# RBB_MCU7_V2_2_MCU.net
KiCad netlist of a schematic drawn in Altium Designer
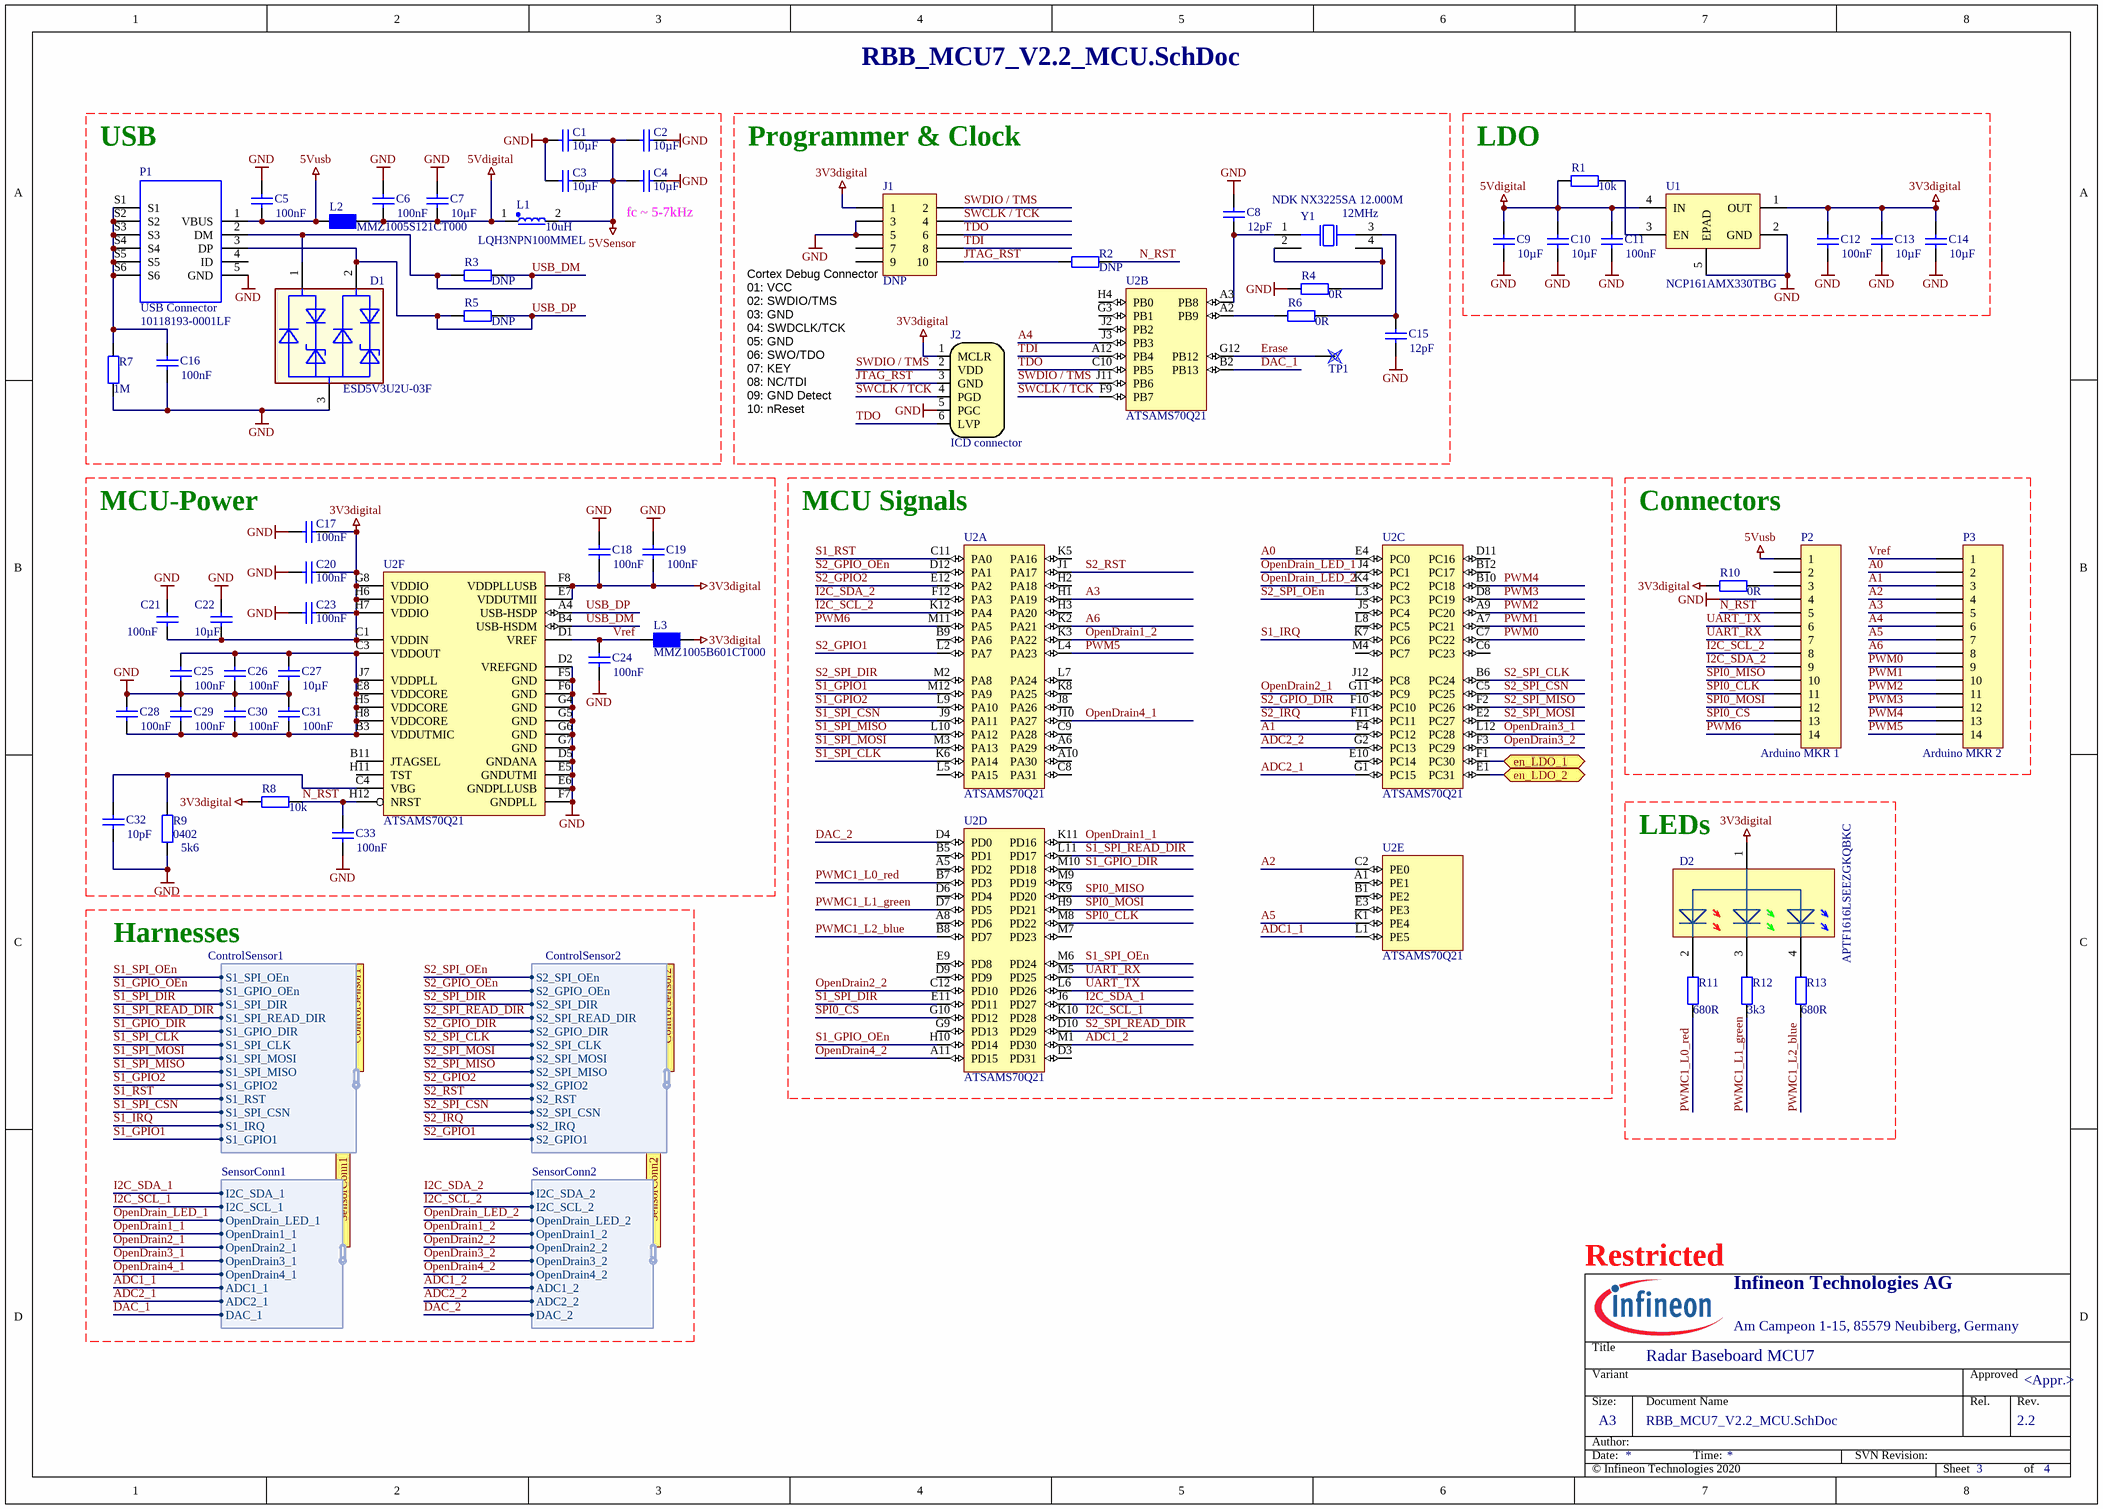
[diagram p0: RBB_MCU7_V2.2_MCU.SchDoc]

(export (version "E")
  (design (tool "Eeschema 10.0.6"))
  (components
    (comp (ref "C1")
      (value "10µF")
      (footprint "0402_C_Axon")
      (description "Capacitor")
      (fields (field (name "PUBLISHER") "Altium Limited"))
      (libsource (lib "Miscellaneous Devices") (part "Cap"))
    )
    (comp (ref "C2")
      (value "10µF")
      (footprint "0402_C_Axon")
      (description "Capacitor")
      (fields (field (name "PUBLISHER") "Altium Limited"))
      (libsource (lib "Miscellaneous Devices") (part "Cap"))
    )
    (comp (ref "C3")
      (value "10µF")
      (footprint "0402_C_Axon")
      (description "Capacitor")
      (fields (field (name "PUBLISHER") "Altium Limited"))
      (libsource (lib "Miscellaneous Devices") (part "Cap"))
    )
    (comp (ref "C4")
      (value "10µF")
      (footprint "0402_C_Axon")
      (description "Capacitor")
      (fields (field (name "PUBLISHER") "Altium Limited"))
      (libsource (lib "Miscellaneous Devices") (part "Cap"))
    )
    (comp (ref "C5")
      (value "100nF")
      (footprint "0402_C_Axon")
      (description "Capacitor")
      (fields (field (name "PUBLISHER") "Altium Limited"))
      (libsource (lib "Miscellaneous Devices") (part "Cap"))
    )
    (comp (ref "C6")
      (value "100nF")
      (footprint "0402_C_Axon")
      (description "Capacitor")
      (fields (field (name "PUBLISHER") "Altium Limited"))
      (libsource (lib "Miscellaneous Devices") (part "Cap"))
    )
    (comp (ref "C7")
      (value "10µF")
      (footprint "0402_C_Axon")
      (description "Capacitor")
      (fields (field (name "PUBLISHER") "Altium Limited"))
      (libsource (lib "Miscellaneous Devices") (part "Cap"))
    )
    (comp (ref "C8")
      (value "12pF")
      (footprint "0402_C_Axon")
      (description "Capacitor")
      (fields (field (name "PUBLISHER") "Altium Limited"))
      (libsource (lib "Miscellaneous Devices") (part "Cap"))
    )
    (comp (ref "C9")
      (value "10µF")
      (footprint "0402_C_Axon")
      (description "Capacitor")
      (fields (field (name "PUBLISHER") "Altium Limited"))
      (libsource (lib "Miscellaneous Devices") (part "Cap"))
    )
    (comp (ref "C10")
      (value "10µF")
      (footprint "0402_C_Axon")
      (description "Capacitor")
      (fields (field (name "PUBLISHER") "Altium Limited"))
      (libsource (lib "Miscellaneous Devices") (part "Cap"))
    )
    (comp (ref "C11")
      (value "100nF")
      (footprint "0402_C_Axon")
      (description "Capacitor")
      (fields (field (name "PUBLISHER") "Altium Limited"))
      (libsource (lib "Miscellaneous Devices") (part "Cap"))
    )
    (comp (ref "C12")
      (value "100nF")
      (footprint "0402_C_Axon")
      (description "Capacitor")
      (fields (field (name "PUBLISHER") "Altium Limited"))
      (libsource (lib "Miscellaneous Devices") (part "Cap"))
    )
    (comp (ref "C13")
      (value "10µF")
      (footprint "0402_C_Axon")
      (description "Capacitor")
      (fields (field (name "PUBLISHER") "Altium Limited"))
      (libsource (lib "Miscellaneous Devices") (part "Cap"))
    )
    (comp (ref "C14")
      (value "10µF")
      (footprint "0402_C_Axon")
      (description "Capacitor")
      (fields (field (name "PUBLISHER") "Altium Limited"))
      (libsource (lib "Miscellaneous Devices") (part "Cap"))
    )
    (comp (ref "C15")
      (value "12pF")
      (footprint "0402_C_Axon")
      (description "Capacitor")
      (fields (field (name "PUBLISHER") "Altium Limited"))
      (libsource (lib "Miscellaneous Devices") (part "Cap"))
    )
    (comp (ref "C16")
      (value "100nF")
      (footprint "0402_C_Axon")
      (description "Capacitor")
      (fields (field (name "PUBLISHER") "Altium Limited"))
      (libsource (lib "Miscellaneous Devices") (part "Cap"))
    )
    (comp (ref "C17")
      (value "100nF")
      (footprint "0402_C_Axon")
      (description "Capacitor")
      (fields (field (name "PUBLISHER") "Altium Limited"))
      (libsource (lib "Miscellaneous Devices") (part "Cap"))
    )
    (comp (ref "C18")
      (value "100nF")
      (footprint "0402_C_Axon")
      (description "Capacitor")
      (fields (field (name "PUBLISHER") "Altium Limited"))
      (libsource (lib "Miscellaneous Devices") (part "Cap"))
    )
    (comp (ref "C19")
      (value "100nF")
      (footprint "0402_C_Axon")
      (description "Capacitor")
      (fields (field (name "PUBLISHER") "Altium Limited"))
      (libsource (lib "Miscellaneous Devices") (part "Cap"))
    )
    (comp (ref "C20")
      (value "100nF")
      (footprint "0402_C_Axon")
      (description "Capacitor")
      (fields (field (name "PUBLISHER") "Altium Limited"))
      (libsource (lib "Miscellaneous Devices") (part "Cap"))
    )
    (comp (ref "C21")
      (value "100nF")
      (footprint "0402_C_Axon")
      (description "Capacitor")
      (fields (field (name "PUBLISHER") "Altium Limited"))
      (libsource (lib "Miscellaneous Devices") (part "Cap"))
    )
    (comp (ref "C22")
      (value "10µF")
      (footprint "0402_C_Axon")
      (description "Capacitor")
      (fields (field (name "PUBLISHER") "Altium Limited"))
      (libsource (lib "Miscellaneous Devices") (part "Cap"))
    )
    (comp (ref "C23")
      (value "100nF")
      (footprint "0402_C_Axon")
      (description "Capacitor")
      (fields (field (name "PUBLISHER") "Altium Limited"))
      (libsource (lib "Miscellaneous Devices") (part "Cap"))
    )
    (comp (ref "C24")
      (value "100nF")
      (footprint "0402_C_Axon")
      (description "Capacitor")
      (fields (field (name "PUBLISHER") "Altium Limited"))
      (libsource (lib "Miscellaneous Devices") (part "Cap"))
    )
    (comp (ref "C25")
      (value "100nF")
      (footprint "0402_C_Axon")
      (description "Capacitor")
      (fields (field (name "PUBLISHER") "Altium Limited"))
      (libsource (lib "Miscellaneous Devices") (part "Cap"))
    )
    (comp (ref "C26")
      (value "100nF")
      (footprint "0402_C_Axon")
      (description "Capacitor")
      (fields (field (name "PUBLISHER") "Altium Limited"))
      (libsource (lib "Miscellaneous Devices") (part "Cap"))
    )
    (comp (ref "C27")
      (value "10µF")
      (footprint "0402_C_Axon")
      (description "Capacitor")
      (fields (field (name "PUBLISHER") "Altium Limited"))
      (libsource (lib "Miscellaneous Devices") (part "Cap"))
    )
    (comp (ref "C28")
      (value "100nF")
      (footprint "0402_C_Axon")
      (description "Capacitor")
      (fields (field (name "PUBLISHER") "Altium Limited"))
      (libsource (lib "Miscellaneous Devices") (part "Cap"))
    )
    (comp (ref "C29")
      (value "100nF")
      (footprint "0402_C_Axon")
      (description "Capacitor")
      (fields (field (name "PUBLISHER") "Altium Limited"))
      (libsource (lib "Miscellaneous Devices") (part "Cap"))
    )
    (comp (ref "C30")
      (value "100nF")
      (footprint "0402_C_Axon")
      (description "Capacitor")
      (fields (field (name "PUBLISHER") "Altium Limited"))
      (libsource (lib "Miscellaneous Devices") (part "Cap"))
    )
    (comp (ref "C31")
      (value "100nF")
      (footprint "0402_C_Axon")
      (description "Capacitor")
      (fields (field (name "PUBLISHER") "Altium Limited"))
      (libsource (lib "Miscellaneous Devices") (part "Cap"))
    )
    (comp (ref "C32")
      (value "10pF")
      (footprint "0402_C_Axon")
      (description "Capacitor")
      (fields (field (name "PUBLISHER") "Altium Limited"))
      (libsource (lib "Miscellaneous Devices") (part "Cap"))
    )
    (comp (ref "C33")
      (value "100nF")
      (footprint "0402_C_Axon")
      (description "Capacitor")
      (fields (field (name "PUBLISHER") "Altium Limited"))
      (libsource (lib "Miscellaneous Devices") (part "Cap"))
    )
    (comp (ref "D1")
      (value "ESD5V3U2U-03F")
      (footprint "SOTFL40P120X59-3N-V")
      (description "Ultra-Low ESD / Transient Protection Diode, Uni-Directional, VRWM 5.3V")
      (fields (field (name "MULTIPLE PART") "No") (field (name "LEGACY PARTNUMBER") "IFX01400970"))
      (libsource (lib "PCBLibraryData") (part "d_unitvs_3p"))
    )
    (comp (ref "D2")
      (value "APTF1616LSEEZGKQBKC")
      (footprint "APTF1616LSEEZGKQBKC")
      (description "Kingbright - APTF1616LSEEZGKQBKC")
      (libsource (lib "Hatvan") (part "APTF1616LSEEZGKQBKC"))
    )
    (comp (ref "J1")
      (value "DNP")
      (footprint "Samtec FTSH-105-01-L-DV-K - no3D")
      (description "Header, 5-Pin, Dual row, SMD")
      (libsource (lib "Sense2Go_V3V1_Release_05102015") (part "Header 5X2"))
    )
    (comp (ref "J2")
      (value "ICD connector")
      (footprint "TC2030-MCP-NL")
      (description "Conector par ICD")
      (fields (field (name "Comment") "DNP"))
      (libsource (lib "Hatvan") (part "TC2030-MCP-NL"))
    )
    (comp (ref "L1")
      (value "LQH3NPN100MMEL")
      (footprint "INDC3030X150N_LQH3NP_MR")
      (description "for Power Line")
      (fields
        (field (name "LEGACY PARTNUMBER") "IND00700877")
        (field (name "MANUFACTURER") "muRata")
        (field (name "ALTIUM_VALUE") "10uH")
      )
      (libsource (lib "PCBLibraryData") (part "IND-SGL-STD-WDG-COR-02P_0000002B"))
    )
    (comp (ref "L2")
      (value "MMZ1005S121CT000")
      (footprint "0402_L_Axon")
      (description "SMD Ferrite Bead")
      (libsource (lib "") (part "INDUCTOR1_1"))
    )
    (comp (ref "L3")
      (value "MMZ1005B601CT000")
      (footprint "0402_L_Axon")
      (description "SMD Ferrite Bead")
      (libsource (lib "Tjuefire") (part "INDUCTOR1"))
    )
    (comp (ref "P1")
      (value "10118193-0001LF")
      (footprint "CON_FCI_10118193")
      (description "USB Micro B Receptacle, Right Angle, SMD w/2 DIP Legs")
      (fields (field (name "ALTIUM_VALUE") "USB Connector") (field (name "MANUFACTURER") "FCI"))
      (libsource (lib "Hatvan") (part "FCI_10118193"))
    )
    (comp (ref "P2")
      (value "Arduino MKR 1")
      (footprint "HDR1X14TOPBOTTOM")
      (description "Header, 14-Pin")
      (fields (field (name "Comment") "DNP") (field (name "PUBLISHER") "Altium Limited"))
      (libsource (lib "Miscellaneous Connectors") (part "Header 14"))
    )
    (comp (ref "P3")
      (value "Arduino MKR 2")
      (footprint "HDR1X14TOPBOTTOM")
      (description "Header, 14-Pin")
      (fields (field (name "Comment") "DNP") (field (name "PUBLISHER") "Altium Limited"))
      (libsource (lib "Miscellaneous Connectors") (part "Header 14"))
    )
    (comp (ref "R1")
      (value "10k")
      (footprint "0402_R_Axon")
      (description "Resistor")
      (libsource (lib "") (part "Res2_2"))
    )
    (comp (ref "R2")
      (value "DNP")
      (footprint "0402_Empty_Axon")
      (description "Resistor")
      (libsource (lib "") (part "Res2_2"))
    )
    (comp (ref "R3")
      (value "DNP")
      (footprint "0402_Empty_Axon")
      (description "Resistor")
      (libsource (lib "") (part "Res2_1"))
    )
    (comp (ref "R4")
      (value "0R")
      (footprint "0402_R_Axon")
      (description "Resistor")
      (libsource (lib "") (part "Res2_2"))
    )
    (comp (ref "R5")
      (value "DNP")
      (footprint "0402_Empty_Axon")
      (description "Resistor")
      (libsource (lib "") (part "Res2_1"))
    )
    (comp (ref "R6")
      (value "0R")
      (footprint "0402_R_Axon")
      (description "Resistor")
      (libsource (lib "") (part "Res2_2"))
    )
    (comp (ref "R7")
      (value "1M")
      (footprint "0402_R_Axon")
      (description "Resistor")
      (libsource (lib "Miscellaneous Devices") (part "Res2"))
    )
    (comp (ref "R8")
      (value "10k")
      (footprint "0402_R_Axon")
      (description "Resistor")
      (libsource (lib "") (part "Res2_1"))
    )
    (comp (ref "R9")
      (value "5k6")
      (footprint "0402_R_Axon")
      (description "Resistor")
      (fields (field (name "ALTIUM_VALUE") "0402"))
      (libsource (lib "") (part "Res2_3"))
    )
    (comp (ref "R10")
      (value "0R")
      (footprint "0402_R_Axon")
      (description "Resistor")
      (libsource (lib "") (part "Res2_2"))
    )
    (comp (ref "R11")
      (value "680R")
      (footprint "0402_R_Axon")
      (description "Resistor")
      (libsource (lib "Miscellaneous Devices") (part "Res2"))
    )
    (comp (ref "R12")
      (value "3k3")
      (footprint "0402_R_Axon")
      (description "Resistor")
      (libsource (lib "Miscellaneous Devices") (part "Res2"))
    )
    (comp (ref "R13")
      (value "680R")
      (footprint "0402_R_Axon")
      (description "Resistor")
      (libsource (lib "Miscellaneous Devices") (part "Res2"))
    )
    (comp (ref "TP1")
      (value "Testpoint")
      (footprint "TP1.5MM")
      (libsource (lib "Hatvan") (part "P_PRUEFPAD"))
    )
    (comp (ref "U1")
      (value "NCP161AMX330TBG")
      (footprint "NCP163")
      (description "NCP161 - LDO 450mA, XDFN4\r\nultra-low noise, high PSRR")
      (libsource (lib "Hatvan") (part "NCP177"))
    )
    (comp (ref "U2")
      (value "ATSAMS70Q21")
      (footprint "LFBGA144")
      (libsource (lib "Hatvan") (part "ATSAMS70Q21"))
    )
    (comp (ref "Y1")
      (value "12MHz")
      (footprint "XTAL-SMD-NX3225SA")
      (description "SMD Crystal Unit for Automotive Application, 12.000MHz")
      (fields
        (field (name "LEGACY PARTNUMBER") "IC02600619")
        (field (name "LEGACY DEVICEID") "NDK NX3225SA 12.000M")
        (field (name "MANUFACTURER") "Nihon Dempa Kogyo")
      )
      (libsource (lib "PCBLibraryData") (part "y_std_4p-1"))
    )
  )
  (nets
    (net (code "5") (name "/A0") (class "Default")
      (node (ref "P3") (pin "2") (pinfunction "2_2") (pintype "passive"))
      (node (ref "U2") (pin "E4") (pinfunction "PC0_E4") (pintype "bidirectional"))
    )
    (net (code "6") (name "/A1") (class "Default")
      (node (ref "P3") (pin "3") (pinfunction "3_3") (pintype "passive"))
      (node (ref "U2") (pin "F4") (pinfunction "PC12_F4") (pintype "bidirectional"))
    )
    (net (code "7") (name "/A2") (class "Default")
      (node (ref "P3") (pin "4") (pinfunction "4_4") (pintype "passive"))
      (node (ref "U2") (pin "C2") (pinfunction "PE0_C2") (pintype "bidirectional"))
    )
    (net (code "8") (name "/A3") (class "Default")
      (node (ref "P3") (pin "5") (pinfunction "5_5") (pintype "passive"))
      (node (ref "U2") (pin "H1") (pinfunction "PA19_H1") (pintype "bidirectional"))
    )
    (net (code "9") (name "/A4") (class "Default")
      (node (ref "P3") (pin "6") (pinfunction "6_6") (pintype "passive"))
      (node (ref "U2") (pin "J3") (pinfunction "PB3_J3") (pintype "bidirectional"))
    )
    (net (code "10") (name "/A5") (class "Default")
      (node (ref "P3") (pin "7") (pinfunction "7_7") (pintype "passive"))
      (node (ref "U2") (pin "K1") (pinfunction "PE4_K1") (pintype "bidirectional"))
    )
    (net (code "11") (name "/A6") (class "Default")
      (node (ref "P3") (pin "8") (pinfunction "8_8") (pintype "passive"))
      (node (ref "U2") (pin "K2") (pinfunction "PA21_K2") (pintype "bidirectional"))
    )
    (net (code "12") (name "/ADC1_1") (class "Default")
      (node (ref "U2") (pin "L1") (pinfunction "PE5_L1") (pintype "bidirectional"))
    )
    (net (code "13") (name "/ADC1_2") (class "Default")
      (node (ref "U2") (pin "M1") (pinfunction "PD30_M1") (pintype "bidirectional"))
    )
    (net (code "14") (name "/ADC2_1") (class "Default")
      (node (ref "U2") (pin "G1") (pinfunction "PC15_G1") (pintype "bidirectional"))
    )
    (net (code "15") (name "/ADC2_2") (class "Default")
      (node (ref "U2") (pin "G2") (pinfunction "PC13_G2") (pintype "bidirectional"))
    )
    (net (code "16") (name "/DAC_1") (class "Default")
      (node (ref "U2") (pin "B2") (pinfunction "PB13_B2") (pintype "bidirectional"))
    )
    (net (code "17") (name "/DAC_2") (class "Default")
      (node (ref "U2") (pin "D4") (pinfunction "PD0_D4") (pintype "bidirectional"))
    )
    (net (code "18") (name "/Erase") (class "Default")
      (node (ref "TP1") (pin "1") (pinfunction "1_1") (pintype "passive"))
      (node (ref "U2") (pin "G12") (pinfunction "PB12_G12") (pintype "bidirectional"))
    )
    (net (code "19") (name "/I2C_SCL_1") (class "Default")
      (node (ref "U2") (pin "K10") (pinfunction "PD28_K10") (pintype "bidirectional"))
    )
    (net (code "20") (name "/I2C_SCL_2") (class "Default")
      (node (ref "P2") (pin "8") (pinfunction "8_8") (pintype "passive"))
      (node (ref "U2") (pin "K12") (pinfunction "PA4_K12") (pintype "bidirectional"))
    )
    (net (code "21") (name "/I2C_SDA_1") (class "Default")
      (node (ref "U2") (pin "J6") (pinfunction "PD27_J6") (pintype "bidirectional"))
    )
    (net (code "22") (name "/I2C_SDA_2") (class "Default")
      (node (ref "P2") (pin "9") (pinfunction "9_9") (pintype "passive"))
      (node (ref "U2") (pin "F12") (pinfunction "PA3_F12") (pintype "bidirectional"))
    )
    (net (code "23") (name "/JTAG_RST") (class "Default")
      (node (ref "J1") (pin "10") (pinfunction "10_10") (pintype "passive"))
      (node (ref "J2") (pin "3") (pinfunction "GND_3") (pintype "passive"))
      (node (ref "R2") (pin "2") (pinfunction "2_2") (pintype "passive"))
    )
    (net (code "24") (name "/N_RST") (class "Default")
      (node (ref "C33") (pin "2") (pinfunction "2_2") (pintype "passive"))
      (node (ref "P2") (pin "5") (pinfunction "5_5") (pintype "passive"))
      (node (ref "R2") (pin "1") (pinfunction "1_1") (pintype "passive"))
      (node (ref "R8") (pin "2") (pinfunction "2_2") (pintype "passive"))
      (node (ref "U2") (pin "H12") (pinfunction "NRST_H12") (pintype "power_in"))
    )
    (net (code "25") (name "/OpenDrain1_1") (class "Default")
      (node (ref "U2") (pin "K11") (pinfunction "PD16_K11") (pintype "bidirectional"))
    )
    (net (code "26") (name "/OpenDrain1_2") (class "Default")
      (node (ref "U2") (pin "K3") (pinfunction "PA22_K3") (pintype "bidirectional"))
    )
    (net (code "27") (name "/OpenDrain2_1") (class "Default")
      (node (ref "U2") (pin "G11") (pinfunction "PC9_G11") (pintype "bidirectional"))
    )
    (net (code "28") (name "/OpenDrain2_2") (class "Default")
      (node (ref "U2") (pin "C12") (pinfunction "PD10_C12") (pintype "bidirectional"))
    )
    (net (code "29") (name "/OpenDrain3_1") (class "Default")
      (node (ref "U2") (pin "L12") (pinfunction "PC28_L12") (pintype "bidirectional"))
    )
    (net (code "30") (name "/OpenDrain3_2") (class "Default")
      (node (ref "U2") (pin "F3") (pinfunction "PC29_F3") (pintype "bidirectional"))
    )
    (net (code "31") (name "/OpenDrain4_1") (class "Default")
      (node (ref "U2") (pin "J10") (pinfunction "PA27_J10") (pintype "bidirectional"))
    )
    (net (code "32") (name "/OpenDrain4_2") (class "Default")
      (node (ref "U2") (pin "A11") (pinfunction "PD15_A11") (pintype "bidirectional"))
    )
    (net (code "33") (name "/OpenDrain_LED_1") (class "Default")
      (node (ref "U2") (pin "J4") (pinfunction "PC1_J4") (pintype "bidirectional"))
    )
    (net (code "34") (name "/OpenDrain_LED_2") (class "Default")
      (node (ref "U2") (pin "K4") (pinfunction "PC2_K4") (pintype "bidirectional"))
    )
    (net (code "35") (name "/PWM0") (class "Default")
      (node (ref "P3") (pin "9") (pinfunction "9_9") (pintype "passive"))
      (node (ref "U2") (pin "C7") (pinfunction "PC22_C7") (pintype "bidirectional"))
    )
    (net (code "36") (name "/PWM1") (class "Default")
      (node (ref "P3") (pin "10") (pinfunction "10_10") (pintype "passive"))
      (node (ref "U2") (pin "A7") (pinfunction "PC21_A7") (pintype "bidirectional"))
    )
    (net (code "37") (name "/PWM2") (class "Default")
      (node (ref "P3") (pin "11") (pinfunction "11_11") (pintype "passive"))
      (node (ref "U2") (pin "A9") (pinfunction "PC20_A9") (pintype "bidirectional"))
    )
    (net (code "38") (name "/PWM3") (class "Default")
      (node (ref "P3") (pin "12") (pinfunction "12_12") (pintype "passive"))
      (node (ref "U2") (pin "D8") (pinfunction "PC19_D8") (pintype "bidirectional"))
    )
    (net (code "39") (name "/PWM4") (class "Default")
      (node (ref "P3") (pin "13") (pinfunction "13_13") (pintype "passive"))
      (node (ref "U2") (pin "B10") (pinfunction "PC18_B10") (pintype "bidirectional"))
    )
    (net (code "40") (name "/PWM5") (class "Default")
      (node (ref "P3") (pin "14") (pinfunction "14_14") (pintype "passive"))
      (node (ref "U2") (pin "L4") (pinfunction "PA23_L4") (pintype "bidirectional"))
    )
    (net (code "41") (name "/PWM6") (class "Default")
      (node (ref "P2") (pin "14") (pinfunction "14_14") (pintype "passive"))
      (node (ref "U2") (pin "M11") (pinfunction "PA5_M11") (pintype "bidirectional"))
    )
    (net (code "42") (name "/PWMC1_L0_red") (class "Default")
      (node (ref "R11") (pin "1") (pinfunction "1_1") (pintype "passive"))
      (node (ref "U2") (pin "B7") (pinfunction "PD3_B7") (pintype "bidirectional"))
    )
    (net (code "43") (name "/PWMC1_L1_green") (class "Default")
      (node (ref "R12") (pin "1") (pinfunction "1_1") (pintype "passive"))
      (node (ref "U2") (pin "D7") (pinfunction "PD5_D7") (pintype "bidirectional"))
    )
    (net (code "44") (name "/PWMC1_L2_blue") (class "Default")
      (node (ref "R13") (pin "1") (pinfunction "1_1") (pintype "passive"))
      (node (ref "U2") (pin "B8") (pinfunction "PD7_B8") (pintype "bidirectional"))
    )
    (net (code "45") (name "/S1_GPIO1") (class "Default")
      (node (ref "U2") (pin "M12") (pinfunction "PA9_M12") (pintype "bidirectional"))
    )
    (net (code "46") (name "/S1_GPIO2") (class "Default")
      (node (ref "U2") (pin "L9") (pinfunction "PA10_L9") (pintype "bidirectional"))
    )
    (net (code "47") (name "/S1_GPIO_DIR") (class "Default")
      (node (ref "U2") (pin "M10") (pinfunction "PD18_M10") (pintype "bidirectional"))
    )
    (net (code "48") (name "/S1_GPIO_OEn") (class "Default")
      (node (ref "U2") (pin "H10") (pinfunction "PD14_H10") (pintype "bidirectional"))
    )
    (net (code "49") (name "/S1_IRQ") (class "Default")
      (node (ref "U2") (pin "K7") (pinfunction "PC6_K7") (pintype "bidirectional"))
    )
    (net (code "50") (name "/S1_RST") (class "Default")
      (node (ref "U2") (pin "C11") (pinfunction "PA0_C11") (pintype "bidirectional"))
    )
    (net (code "51") (name "/S1_SPI_CLK") (class "Default")
      (node (ref "U2") (pin "K6") (pinfunction "PA14_K6") (pintype "bidirectional"))
    )
    (net (code "52") (name "/S1_SPI_CSN") (class "Default")
      (node (ref "U2") (pin "J9") (pinfunction "PA11_J9") (pintype "bidirectional"))
    )
    (net (code "53") (name "/S1_SPI_DIR") (class "Default")
      (node (ref "U2") (pin "E11") (pinfunction "PD11_E11") (pintype "bidirectional"))
    )
    (net (code "54") (name "/S1_SPI_MISO") (class "Default")
      (node (ref "U2") (pin "L10") (pinfunction "PA12_L10") (pintype "bidirectional"))
    )
    (net (code "55") (name "/S1_SPI_MOSI") (class "Default")
      (node (ref "U2") (pin "M3") (pinfunction "PA13_M3") (pintype "bidirectional"))
    )
    (net (code "56") (name "/S1_SPI_OEn") (class "Default")
      (node (ref "U2") (pin "M6") (pinfunction "PD24_M6") (pintype "bidirectional"))
    )
    (net (code "57") (name "/S1_SPI_READ_DIR") (class "Default")
      (node (ref "U2") (pin "L11") (pinfunction "PD17_L11") (pintype "bidirectional"))
    )
    (net (code "58") (name "/S2_GPIO1") (class "Default")
      (node (ref "U2") (pin "L2") (pinfunction "PA7_L2") (pintype "bidirectional"))
    )
    (net (code "59") (name "/S2_GPIO2") (class "Default")
      (node (ref "U2") (pin "E12") (pinfunction "PA2_E12") (pintype "bidirectional"))
    )
    (net (code "60") (name "/S2_GPIO_DIR") (class "Default")
      (node (ref "U2") (pin "F10") (pinfunction "PC10_F10") (pintype "bidirectional"))
    )
    (net (code "61") (name "/S2_GPIO_OEn") (class "Default")
      (node (ref "U2") (pin "D12") (pinfunction "PA1_D12") (pintype "bidirectional"))
    )
    (net (code "62") (name "/S2_IRQ") (class "Default")
      (node (ref "U2") (pin "F11") (pinfunction "PC11_F11") (pintype "bidirectional"))
    )
    (net (code "63") (name "/S2_RST") (class "Default")
      (node (ref "U2") (pin "J1") (pinfunction "PA17_J1") (pintype "bidirectional"))
    )
    (net (code "64") (name "/S2_SPI_CLK") (class "Default")
      (node (ref "U2") (pin "B6") (pinfunction "PC24_B6") (pintype "bidirectional"))
    )
    (net (code "65") (name "/S2_SPI_CSN") (class "Default")
      (node (ref "U2") (pin "C5") (pinfunction "PC25_C5") (pintype "bidirectional"))
    )
    (net (code "66") (name "/S2_SPI_DIR") (class "Default")
      (node (ref "U2") (pin "M2") (pinfunction "PA8_M2") (pintype "bidirectional"))
    )
    (net (code "67") (name "/S2_SPI_MISO") (class "Default")
      (node (ref "U2") (pin "F2") (pinfunction "PC26_F2") (pintype "bidirectional"))
    )
    (net (code "68") (name "/S2_SPI_MOSI") (class "Default")
      (node (ref "U2") (pin "E2") (pinfunction "PC27_E2") (pintype "bidirectional"))
    )
    (net (code "69") (name "/S2_SPI_OEn") (class "Default")
      (node (ref "U2") (pin "L3") (pinfunction "PC3_L3") (pintype "bidirectional"))
    )
    (net (code "70") (name "/S2_SPI_READ_DIR") (class "Default")
      (node (ref "U2") (pin "D10") (pinfunction "PD29_D10") (pintype "bidirectional"))
    )
    (net (code "71") (name "/SPI0_CLK") (class "Default")
      (node (ref "P2") (pin "11") (pinfunction "11_11") (pintype "passive"))
      (node (ref "U2") (pin "M8") (pinfunction "PD22_M8") (pintype "bidirectional"))
    )
    (net (code "72") (name "/SPI0_CS") (class "Default")
      (node (ref "P2") (pin "13") (pinfunction "13_13") (pintype "passive"))
      (node (ref "U2") (pin "G10") (pinfunction "PD12_G10") (pintype "bidirectional"))
    )
    (net (code "73") (name "/SPI0_MISO") (class "Default")
      (node (ref "P2") (pin "10") (pinfunction "10_10") (pintype "passive"))
      (node (ref "U2") (pin "K9") (pinfunction "PD20_K9") (pintype "bidirectional"))
    )
    (net (code "74") (name "/SPI0_MOSI") (class "Default")
      (node (ref "P2") (pin "12") (pinfunction "12_12") (pintype "passive"))
      (node (ref "U2") (pin "H9") (pinfunction "PD21_H9") (pintype "bidirectional"))
    )
    (net (code "75") (name "/SWCLK {slash} TCK") (class "Default")
      (node (ref "J1") (pin "4") (pinfunction "4_4") (pintype "passive"))
      (node (ref "J2") (pin "4") (pinfunction "PGD_4") (pintype "passive"))
      (node (ref "U2") (pin "F9") (pinfunction "PB7_F9") (pintype "bidirectional"))
    )
    (net (code "76") (name "/SWDIO {slash} TMS") (class "Default")
      (node (ref "J1") (pin "2") (pinfunction "2_2") (pintype "passive"))
      (node (ref "J2") (pin "2") (pinfunction "VDD_2") (pintype "passive"))
      (node (ref "U2") (pin "J11") (pinfunction "PB6_J11") (pintype "bidirectional"))
    )
    (net (code "77") (name "/TDI") (class "Default")
      (node (ref "J1") (pin "8") (pinfunction "8_8") (pintype "passive"))
      (node (ref "U2") (pin "A12") (pinfunction "PB4_A12") (pintype "bidirectional"))
    )
    (net (code "78") (name "/TDO") (class "Default")
      (node (ref "J1") (pin "6") (pinfunction "6_6") (pintype "passive"))
      (node (ref "J2") (pin "6") (pinfunction "LVP_6") (pintype "passive"))
      (node (ref "U2") (pin "C10") (pinfunction "PB5_C10") (pintype "bidirectional"))
    )
    (net (code "79") (name "/UART_RX") (class "Default")
      (node (ref "P2") (pin "7") (pinfunction "7_7") (pintype "passive"))
      (node (ref "U2") (pin "M5") (pinfunction "PD25_M5") (pintype "bidirectional"))
    )
    (net (code "80") (name "/UART_TX") (class "Default")
      (node (ref "P2") (pin "6") (pinfunction "6_6") (pintype "passive"))
      (node (ref "U2") (pin "L6") (pinfunction "PD26_L6") (pintype "bidirectional"))
    )
    (net (code "81") (name "/USB_DM") (class "Default")
      (node (ref "D1") (pin "1") (pinfunction "1_1") (pintype "passive"))
      (node (ref "P1") (pin "2") (pinfunction "DM_2") (pintype "passive"))
      (node (ref "R3") (pin "1") (pinfunction "1_1") (pintype "passive"))
      (node (ref "R3") (pin "2") (pinfunction "2_2") (pintype "passive"))
      (node (ref "U2") (pin "B4") (pinfunction "USB-HSDM_B4") (pintype "bidirectional"))
    )
    (net (code "82") (name "/USB_DP") (class "Default")
      (node (ref "D1") (pin "2") (pinfunction "2_2") (pintype "passive"))
      (node (ref "P1") (pin "3") (pinfunction "DP_3") (pintype "passive"))
      (node (ref "R5") (pin "1") (pinfunction "1_1") (pintype "passive"))
      (node (ref "R5") (pin "2") (pinfunction "2_2") (pintype "passive"))
      (node (ref "U2") (pin "A4") (pinfunction "USB-HSDP_A4") (pintype "bidirectional"))
    )
    (net (code "83") (name "/Vref") (class "Default")
      (node (ref "C24") (pin "2") (pinfunction "2_2") (pintype "passive"))
      (node (ref "L3") (pin "2") (pinfunction "2_2") (pintype "passive"))
      (node (ref "P3") (pin "1") (pinfunction "1_1") (pintype "passive"))
      (node (ref "U2") (pin "D1") (pinfunction "VREF_D1") (pintype "power_in"))
    )
    (net (code "84") (name "/en_LDO_1") (class "Default")
      (node (ref "U2") (pin "F1") (pinfunction "PC30_F1") (pintype "bidirectional"))
    )
    (net (code "85") (name "/en_LDO_2") (class "Default")
      (node (ref "U2") (pin "E1") (pinfunction "PC31_E1") (pintype "bidirectional"))
    )
    (net (code "90") (name "3V3digital") (class "Default")
      (node (ref "C12") (pin "2") (pinfunction "2_2") (pintype "passive"))
      (node (ref "C13") (pin "2") (pinfunction "2_2") (pintype "passive"))
      (node (ref "C14") (pin "2") (pinfunction "2_2") (pintype "passive"))
      (node (ref "C17") (pin "1") (pinfunction "1_1") (pintype "passive"))
      (node (ref "C18") (pin "1") (pinfunction "1_1") (pintype "passive"))
      (node (ref "C19") (pin "1") (pinfunction "1_1") (pintype "passive"))
      (node (ref "C20") (pin "1") (pinfunction "1_1") (pintype "passive"))
      (node (ref "C21") (pin "1") (pinfunction "1_1") (pintype "passive"))
      (node (ref "C22") (pin "1") (pinfunction "1_1") (pintype "passive"))
      (node (ref "C23") (pin "1") (pinfunction "1_1") (pintype "passive"))
      (node (ref "D2") (pin "1") (pinfunction "1_1") (pintype "passive"))
      (node (ref "J1") (pin "1") (pinfunction "1_1") (pintype "passive"))
      (node (ref "J2") (pin "1") (pinfunction "MCLR_1") (pintype "passive"))
      (node (ref "L3") (pin "1") (pinfunction "1_1") (pintype "passive"))
      (node (ref "R10") (pin "2") (pinfunction "2_2") (pintype "passive"))
      (node (ref "R8") (pin "1") (pinfunction "1_1") (pintype "passive"))
      (node (ref "U1") (pin "1") (pinfunction "OUT_1") (pintype "passive"))
      (node (ref "U2") (pin "C1") (pinfunction "VDDIN_C1") (pintype "power_in"))
      (node (ref "U2") (pin "E7") (pinfunction "VDDUTMII_E7") (pintype "power_in"))
      (node (ref "U2") (pin "F8") (pinfunction "VDDPLLUSB_F8") (pintype "power_in"))
      (node (ref "U2") (pin "G8") (pinfunction "VDDIO_G8") (pintype "power_in"))
      (node (ref "U2") (pin "H6") (pinfunction "VDDIO_H6") (pintype "power_in"))
      (node (ref "U2") (pin "H7") (pinfunction "VDDIO_H7") (pintype "power_in"))
    )
    (net (code "91") (name "5VSensor") (class "Default")
      (node (ref "C1") (pin "2") (pinfunction "2_2") (pintype "passive"))
      (node (ref "C2") (pin "2") (pinfunction "2_2") (pintype "passive"))
      (node (ref "C3") (pin "2") (pinfunction "2_2") (pintype "passive"))
      (node (ref "C4") (pin "2") (pinfunction "2_2") (pintype "passive"))
      (node (ref "L1") (pin "2") (pinfunction "2_2") (pintype "passive"))
    )
    (net (code "92") (name "5Vdigital") (class "Default")
      (node (ref "C10") (pin "2") (pinfunction "2_2") (pintype "passive"))
      (node (ref "C11") (pin "2") (pinfunction "2_2") (pintype "passive"))
      (node (ref "C6") (pin "2") (pinfunction "2_2") (pintype "passive"))
      (node (ref "C7") (pin "2") (pinfunction "2_2") (pintype "passive"))
      (node (ref "C9") (pin "2") (pinfunction "2_2") (pintype "passive"))
      (node (ref "L1") (pin "1") (pinfunction "1_1") (pintype "passive"))
      (node (ref "L2") (pin "2") (pinfunction "2_2") (pintype "passive"))
      (node (ref "R1") (pin "2") (pinfunction "2_2") (pintype "passive"))
      (node (ref "U1") (pin "4") (pinfunction "IN_4") (pintype "passive"))
    )
    (net (code "93") (name "5Vusb") (class "Default")
      (node (ref "C5") (pin "2") (pinfunction "2_2") (pintype "passive"))
      (node (ref "L2") (pin "1") (pinfunction "1_1") (pintype "passive"))
      (node (ref "P1") (pin "1") (pinfunction "VBUS_1") (pintype "passive"))
      (node (ref "P2") (pin "1") (pinfunction "1_1") (pintype "passive"))
    )
    (net (code "94") (name "GND") (class "Default")
      (node (ref "C1") (pin "1") (pinfunction "1_1") (pintype "passive"))
      (node (ref "C10") (pin "1") (pinfunction "1_1") (pintype "passive"))
      (node (ref "C11") (pin "1") (pinfunction "1_1") (pintype "passive"))
      (node (ref "C12") (pin "1") (pinfunction "1_1") (pintype "passive"))
      (node (ref "C13") (pin "1") (pinfunction "1_1") (pintype "passive"))
      (node (ref "C14") (pin "1") (pinfunction "1_1") (pintype "passive"))
      (node (ref "C15") (pin "2") (pinfunction "2_2") (pintype "passive"))
      (node (ref "C16") (pin "2") (pinfunction "2_2") (pintype "passive"))
      (node (ref "C17") (pin "2") (pinfunction "2_2") (pintype "passive"))
      (node (ref "C18") (pin "2") (pinfunction "2_2") (pintype "passive"))
      (node (ref "C19") (pin "2") (pinfunction "2_2") (pintype "passive"))
      (node (ref "C2") (pin "1") (pinfunction "1_1") (pintype "passive"))
      (node (ref "C20") (pin "2") (pinfunction "2_2") (pintype "passive"))
      (node (ref "C21") (pin "2") (pinfunction "2_2") (pintype "passive"))
      (node (ref "C22") (pin "2") (pinfunction "2_2") (pintype "passive"))
      (node (ref "C23") (pin "2") (pinfunction "2_2") (pintype "passive"))
      (node (ref "C24") (pin "1") (pinfunction "1_1") (pintype "passive"))
      (node (ref "C25") (pin "1") (pinfunction "1_1") (pintype "passive"))
      (node (ref "C26") (pin "1") (pinfunction "1_1") (pintype "passive"))
      (node (ref "C27") (pin "2") (pinfunction "2_2") (pintype "passive"))
      (node (ref "C28") (pin "2") (pinfunction "2_2") (pintype "passive"))
      (node (ref "C29") (pin "2") (pinfunction "2_2") (pintype "passive"))
      (node (ref "C3") (pin "1") (pinfunction "1_1") (pintype "passive"))
      (node (ref "C30") (pin "2") (pinfunction "2_2") (pintype "passive"))
      (node (ref "C31") (pin "2") (pinfunction "2_2") (pintype "passive"))
      (node (ref "C32") (pin "1") (pinfunction "1_1") (pintype "passive"))
      (node (ref "C33") (pin "1") (pinfunction "1_1") (pintype "passive"))
      (node (ref "C4") (pin "1") (pinfunction "1_1") (pintype "passive"))
      (node (ref "C5") (pin "1") (pinfunction "1_1") (pintype "passive"))
      (node (ref "C6") (pin "1") (pinfunction "1_1") (pintype "passive"))
      (node (ref "C7") (pin "1") (pinfunction "1_1") (pintype "passive"))
      (node (ref "C8") (pin "1") (pinfunction "1_1") (pintype "passive"))
      (node (ref "C9") (pin "1") (pinfunction "1_1") (pintype "passive"))
      (node (ref "D1") (pin "3") (pinfunction "3_3") (pintype "passive"))
      (node (ref "J1") (pin "3") (pinfunction "3_3") (pintype "passive"))
      (node (ref "J1") (pin "5") (pinfunction "5_5") (pintype "passive"))
      (node (ref "J2") (pin "5") (pinfunction "PGC_5") (pintype "passive"))
      (node (ref "P1") (pin "5") (pinfunction "GND_5") (pintype "passive"))
      (node (ref "P2") (pin "4") (pinfunction "4_4") (pintype "passive"))
      (node (ref "R4") (pin "2") (pinfunction "2_2") (pintype "passive"))
      (node (ref "R7") (pin "1") (pinfunction "1_1") (pintype "passive"))
      (node (ref "R9") (pin "2") (pinfunction "2_2") (pintype "passive"))
      (node (ref "U1") (pin "2") (pinfunction "GND_2") (pintype "passive"))
      (node (ref "U1") (pin "5") (pinfunction "EPAD_5") (pintype "passive"))
      (node (ref "U2") (pin "D2") (pinfunction "VREFGND_D2") (pintype "power_in"))
      (node (ref "U2") (pin "D5") (pinfunction "GNDANA_D5") (pintype "power_in"))
      (node (ref "U2") (pin "E5") (pinfunction "GNDUTMI_E5") (pintype "power_in"))
      (node (ref "U2") (pin "E6") (pinfunction "GNDPLLUSB_E6") (pintype "power_in"))
      (node (ref "U2") (pin "F5") (pinfunction "GND_F5") (pintype "power_in"))
      (node (ref "U2") (pin "F6") (pinfunction "GND_F6") (pintype "power_in"))
      (node (ref "U2") (pin "F7") (pinfunction "GNDPLL_F7") (pintype "power_in"))
      (node (ref "U2") (pin "G4") (pinfunction "GND_G4") (pintype "power_in"))
      (node (ref "U2") (pin "G5") (pinfunction "GND_G5") (pintype "power_in"))
      (node (ref "U2") (pin "G6") (pinfunction "GND_G6") (pintype "power_in"))
      (node (ref "U2") (pin "G7") (pinfunction "GND_G7") (pintype "power_in"))
    )
    (net (code "95") (name "Net-(C15-Pad1)") (class "Default")
      (node (ref "C15") (pin "1") (pinfunction "1_1") (pintype "passive"))
      (node (ref "R6") (pin "1") (pinfunction "1_1") (pintype "passive"))
      (node (ref "Y1") (pin "3") (pinfunction "3_3") (pintype "passive"))
    )
    (net (code "96") (name "Net-(C16-Pad1)") (class "Default")
      (node (ref "C16") (pin "1") (pinfunction "1_1") (pintype "passive"))
      (node (ref "P1") (pin "S1") (pinfunction "S1_S1") (pintype "passive"))
      (node (ref "P1") (pin "S2") (pinfunction "S2_S2") (pintype "passive"))
      (node (ref "P1") (pin "S3") (pinfunction "S3_S3") (pintype "passive"))
      (node (ref "P1") (pin "S4") (pinfunction "S4_S4") (pintype "passive"))
      (node (ref "P1") (pin "S5") (pinfunction "S5_S5") (pintype "passive"))
      (node (ref "P1") (pin "S6") (pinfunction "S6_S6") (pintype "passive"))
      (node (ref "R7") (pin "2") (pinfunction "2_2") (pintype "passive"))
    )
    (net (code "97") (name "Net-(D2-Pad2)") (class "Default")
      (node (ref "D2") (pin "2") (pinfunction "2_2") (pintype "passive"))
      (node (ref "R11") (pin "2") (pinfunction "2_2") (pintype "passive"))
    )
    (net (code "98") (name "Net-(D2-Pad3)") (class "Default")
      (node (ref "D2") (pin "3") (pinfunction "3_3") (pintype "passive"))
      (node (ref "R12") (pin "2") (pinfunction "2_2") (pintype "passive"))
    )
    (net (code "99") (name "Net-(D2-Pad4)") (class "Default")
      (node (ref "D2") (pin "4") (pinfunction "4_4") (pintype "passive"))
      (node (ref "R13") (pin "2") (pinfunction "2_2") (pintype "passive"))
    )
    (net (code "100") (name "Net-(P2-Pad3)") (class "Default")
      (node (ref "P2") (pin "3") (pinfunction "3_3") (pintype "passive"))
      (node (ref "R10") (pin "1") (pinfunction "1_1") (pintype "passive"))
    )
    (net (code "101") (name "Net-(R4-Pad1)") (class "Default")
      (node (ref "R4") (pin "1") (pinfunction "1_1") (pintype "passive"))
      (node (ref "Y1") (pin "2") (pinfunction "2_2") (pintype "power_in"))
      (node (ref "Y1") (pin "4") (pinfunction "4_4") (pintype "power_in"))
    )
    (net (code "102") (name "Net-(U1-EN)") (class "Default")
      (node (ref "R1") (pin "1") (pinfunction "1_1") (pintype "passive"))
      (node (ref "U1") (pin "3") (pinfunction "EN_3") (pintype "passive"))
    )
    (net (code "103") (name "Net-(U2B-PB8)") (class "Default")
      (node (ref "C8") (pin "2") (pinfunction "2_2") (pintype "passive"))
      (node (ref "U2") (pin "A3") (pinfunction "PB8_A3") (pintype "bidirectional"))
      (node (ref "Y1") (pin "1") (pinfunction "1_1") (pintype "passive"))
    )
    (net (code "104") (name "Net-(U2B-PB9)") (class "Default")
      (node (ref "R6") (pin "2") (pinfunction "2_2") (pintype "passive"))
      (node (ref "U2") (pin "A2") (pinfunction "PB9_A2") (pintype "bidirectional"))
    )
    (net (code "105") (name "Net-(U2F-VBG)") (class "Default")
      (node (ref "C32") (pin "2") (pinfunction "2_2") (pintype "passive"))
      (node (ref "R9") (pin "1") (pinfunction "1_1") (pintype "passive"))
      (node (ref "U2") (pin "C4") (pinfunction "VBG_C4") (pintype "power_in"))
    )
    (net (code "106") (name "Net-(U2F-VDDOUT)") (class "Default")
      (node (ref "C25") (pin "2") (pinfunction "2_2") (pintype "passive"))
      (node (ref "C26") (pin "2") (pinfunction "2_2") (pintype "passive"))
      (node (ref "C27") (pin "1") (pinfunction "1_1") (pintype "passive"))
      (node (ref "C28") (pin "1") (pinfunction "1_1") (pintype "passive"))
      (node (ref "C29") (pin "1") (pinfunction "1_1") (pintype "passive"))
      (node (ref "C30") (pin "1") (pinfunction "1_1") (pintype "passive"))
      (node (ref "C31") (pin "1") (pinfunction "1_1") (pintype "passive"))
      (node (ref "U2") (pin "B3") (pinfunction "VDDUTMIC_B3") (pintype "power_in"))
      (node (ref "U2") (pin "C3") (pinfunction "VDDOUT_C3") (pintype "power_in"))
      (node (ref "U2") (pin "E8") (pinfunction "VDDCORE_E8") (pintype "power_in"))
      (node (ref "U2") (pin "H5") (pinfunction "VDDCORE_H5") (pintype "power_in"))
      (node (ref "U2") (pin "H8") (pinfunction "VDDCORE_H8") (pintype "power_in"))
      (node (ref "U2") (pin "J7") (pinfunction "VDDPLL_J7") (pintype "power_in"))
    )
    (net (code "107") (name "unconnected-(J1-Pad7)") (class "Default")
      (node (ref "J1") (pin "7") (pinfunction "7_7") (pintype "passive"))
    )
    (net (code "108") (name "unconnected-(J1-Pad9)") (class "Default")
      (node (ref "J1") (pin "9") (pinfunction "9_9") (pintype "passive"))
    )
    (net (code "109") (name "unconnected-(P1-ID-Pad4)") (class "Default")
      (node (ref "P1") (pin "4") (pinfunction "ID_4") (pintype "passive"))
    )
    (net (code "110") (name "unconnected-(P2-Pad2)") (class "Default")
      (node (ref "P2") (pin "2") (pinfunction "2_2") (pintype "passive"))
    )
    (net (code "111") (name "unconnected-(U2A-PA6-PadB9)") (class "Default")
      (node (ref "U2") (pin "B9") (pinfunction "PA6_B9") (pintype "bidirectional"))
    )
    (net (code "112") (name "unconnected-(U2A-PA15-PadL5)") (class "Default")
      (node (ref "U2") (pin "L5") (pinfunction "PA15_L5") (pintype "bidirectional"))
    )
    (net (code "113") (name "unconnected-(U2A-PA16-PadK5)") (class "Default")
      (node (ref "U2") (pin "K5") (pinfunction "PA16_K5") (pintype "bidirectional"))
    )
    (net (code "114") (name "unconnected-(U2A-PA18-PadH2)") (class "Default")
      (node (ref "U2") (pin "H2") (pinfunction "PA18_H2") (pintype "bidirectional"))
    )
    (net (code "115") (name "unconnected-(U2A-PA20-PadH3)") (class "Default")
      (node (ref "U2") (pin "H3") (pinfunction "PA20_H3") (pintype "bidirectional"))
    )
    (net (code "116") (name "unconnected-(U2A-PA24-PadL7)") (class "Default")
      (node (ref "U2") (pin "L7") (pinfunction "PA24_L7") (pintype "bidirectional"))
    )
    (net (code "117") (name "unconnected-(U2A-PA25-PadK8)") (class "Default")
      (node (ref "U2") (pin "K8") (pinfunction "PA25_K8") (pintype "bidirectional"))
    )
    (net (code "118") (name "unconnected-(U2A-PA26-PadJ8)") (class "Default")
      (node (ref "U2") (pin "J8") (pinfunction "PA26_J8") (pintype "bidirectional"))
    )
    (net (code "119") (name "unconnected-(U2A-PA28-PadC9)") (class "Default")
      (node (ref "U2") (pin "C9") (pinfunction "PA28_C9") (pintype "bidirectional"))
    )
    (net (code "120") (name "unconnected-(U2A-PA29-PadA6)") (class "Default")
      (node (ref "U2") (pin "A6") (pinfunction "PA29_A6") (pintype "bidirectional"))
    )
    (net (code "121") (name "unconnected-(U2A-PA30-PadA10)") (class "Default")
      (node (ref "U2") (pin "A10") (pinfunction "PA30_A10") (pintype "bidirectional"))
    )
    (net (code "122") (name "unconnected-(U2A-PA31-PadC8)") (class "Default")
      (node (ref "U2") (pin "C8") (pinfunction "PA31_C8") (pintype "bidirectional"))
    )
    (net (code "123") (name "unconnected-(U2B-PB0-PadH4)") (class "Default")
      (node (ref "U2") (pin "H4") (pinfunction "PB0_H4") (pintype "bidirectional"))
    )
    (net (code "124") (name "unconnected-(U2B-PB1-PadG3)") (class "Default")
      (node (ref "U2") (pin "G3") (pinfunction "PB1_G3") (pintype "bidirectional"))
    )
    (net (code "125") (name "unconnected-(U2B-PB2-PadJ2)") (class "Default")
      (node (ref "U2") (pin "J2") (pinfunction "PB2_J2") (pintype "bidirectional"))
    )
    (net (code "126") (name "unconnected-(U2C-PC4-PadJ5)") (class "Default")
      (node (ref "U2") (pin "J5") (pinfunction "PC4_J5") (pintype "bidirectional"))
    )
    (net (code "127") (name "unconnected-(U2C-PC5-PadL8)") (class "Default")
      (node (ref "U2") (pin "L8") (pinfunction "PC5_L8") (pintype "bidirectional"))
    )
    (net (code "128") (name "unconnected-(U2C-PC7-PadM4)") (class "Default")
      (node (ref "U2") (pin "M4") (pinfunction "PC7_M4") (pintype "bidirectional"))
    )
    (net (code "129") (name "unconnected-(U2C-PC8-PadJ12)") (class "Default")
      (node (ref "U2") (pin "J12") (pinfunction "PC8_J12") (pintype "bidirectional"))
    )
    (net (code "130") (name "unconnected-(U2C-PC14-PadE10)") (class "Default")
      (node (ref "U2") (pin "E10") (pinfunction "PC14_E10") (pintype "bidirectional"))
    )
    (net (code "131") (name "unconnected-(U2C-PC16-PadD11)") (class "Default")
      (node (ref "U2") (pin "D11") (pinfunction "PC16_D11") (pintype "bidirectional"))
    )
    (net (code "132") (name "unconnected-(U2C-PC17-PadB12)") (class "Default")
      (node (ref "U2") (pin "B12") (pinfunction "PC17_B12") (pintype "bidirectional"))
    )
    (net (code "133") (name "unconnected-(U2C-PC23-PadC6)") (class "Default")
      (node (ref "U2") (pin "C6") (pinfunction "PC23_C6") (pintype "bidirectional"))
    )
    (net (code "134") (name "unconnected-(U2D-PD1-PadB5)") (class "Default")
      (node (ref "U2") (pin "B5") (pinfunction "PD1_B5") (pintype "bidirectional"))
    )
    (net (code "135") (name "unconnected-(U2D-PD2-PadA5)") (class "Default")
      (node (ref "U2") (pin "A5") (pinfunction "PD2_A5") (pintype "bidirectional"))
    )
    (net (code "136") (name "unconnected-(U2D-PD4-PadD6)") (class "Default")
      (node (ref "U2") (pin "D6") (pinfunction "PD4_D6") (pintype "bidirectional"))
    )
    (net (code "137") (name "unconnected-(U2D-PD6-PadA8)") (class "Default")
      (node (ref "U2") (pin "A8") (pinfunction "PD6_A8") (pintype "bidirectional"))
    )
    (net (code "138") (name "unconnected-(U2D-PD8-PadE9)") (class "Default")
      (node (ref "U2") (pin "E9") (pinfunction "PD8_E9") (pintype "bidirectional"))
    )
    (net (code "139") (name "unconnected-(U2D-PD9-PadD9)") (class "Default")
      (node (ref "U2") (pin "D9") (pinfunction "PD9_D9") (pintype "bidirectional"))
    )
    (net (code "140") (name "unconnected-(U2D-PD13-PadG9)") (class "Default")
      (node (ref "U2") (pin "G9") (pinfunction "PD13_G9") (pintype "bidirectional"))
    )
    (net (code "141") (name "unconnected-(U2D-PD19-PadM9)") (class "Default")
      (node (ref "U2") (pin "M9") (pinfunction "PD19_M9") (pintype "bidirectional"))
    )
    (net (code "142") (name "unconnected-(U2D-PD23-PadM7)") (class "Default")
      (node (ref "U2") (pin "M7") (pinfunction "PD23_M7") (pintype "bidirectional"))
    )
    (net (code "143") (name "unconnected-(U2D-PD31-PadD3)") (class "Default")
      (node (ref "U2") (pin "D3") (pinfunction "PD31_D3") (pintype "bidirectional"))
    )
    (net (code "144") (name "unconnected-(U2E-PE1-PadA1)") (class "Default")
      (node (ref "U2") (pin "A1") (pinfunction "PE1_A1") (pintype "bidirectional"))
    )
    (net (code "145") (name "unconnected-(U2E-PE2-PadB1)") (class "Default")
      (node (ref "U2") (pin "B1") (pinfunction "PE2_B1") (pintype "bidirectional"))
    )
    (net (code "146") (name "unconnected-(U2E-PE3-PadE3)") (class "Default")
      (node (ref "U2") (pin "E3") (pinfunction "PE3_E3") (pintype "bidirectional"))
    )
    (net (code "147") (name "unconnected-(U2F-JTAGSEL-PadB11)") (class "Default")
      (node (ref "U2") (pin "B11") (pinfunction "JTAGSEL_B11") (pintype "power_in"))
    )
    (net (code "148") (name "unconnected-(U2F-TST-PadH11)") (class "Default")
      (node (ref "U2") (pin "H11") (pinfunction "TST_H11") (pintype "power_in"))
    )
  )
)
